# Main.net
KiCad netlist of a schematic drawn in Altium Designer
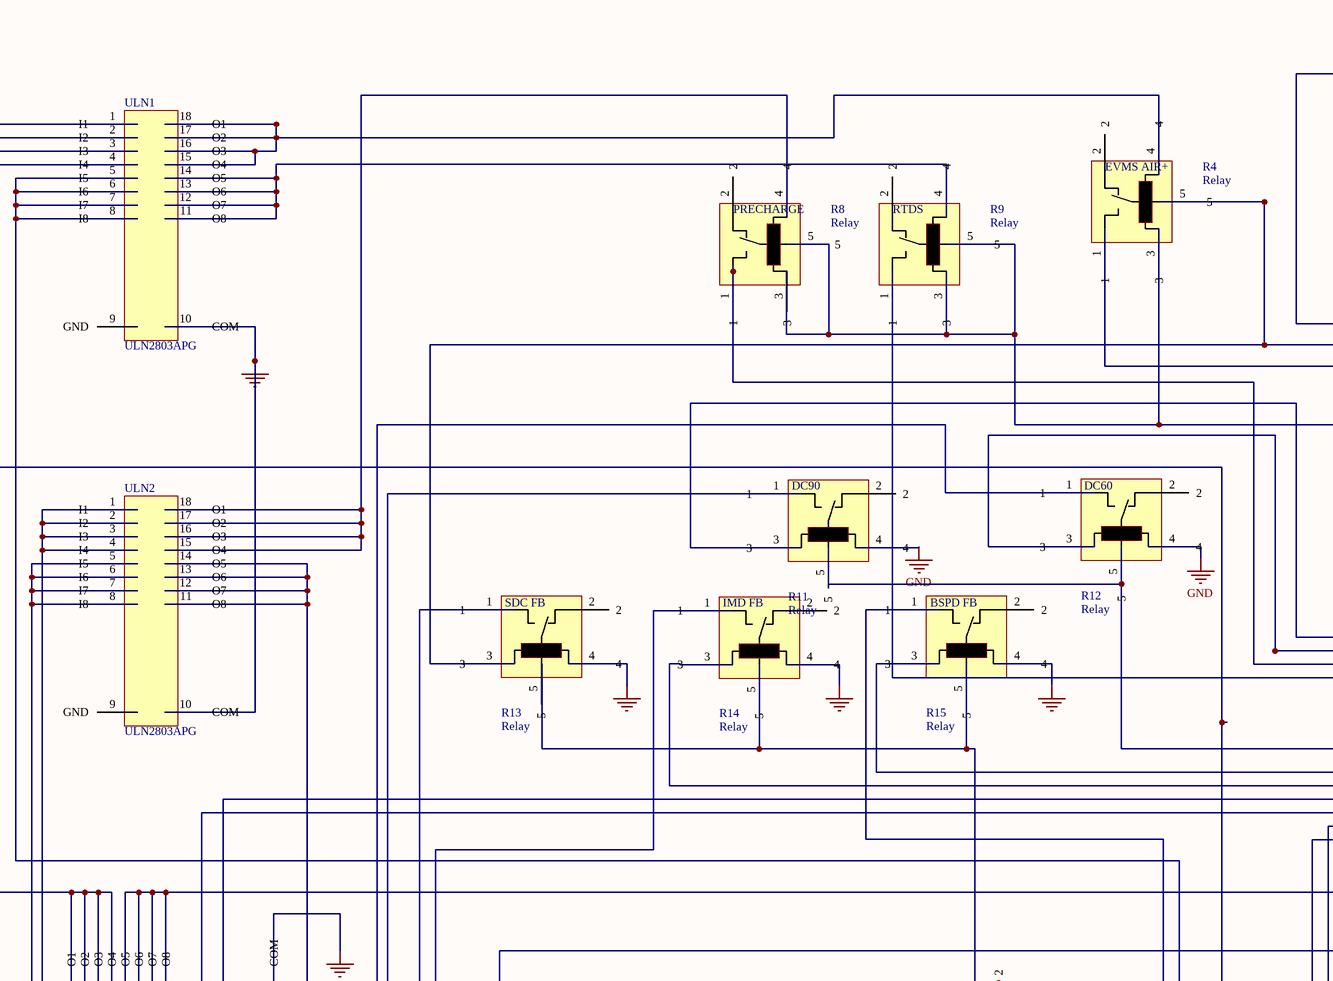
[diagram p0: Main.SchDoc, top left]
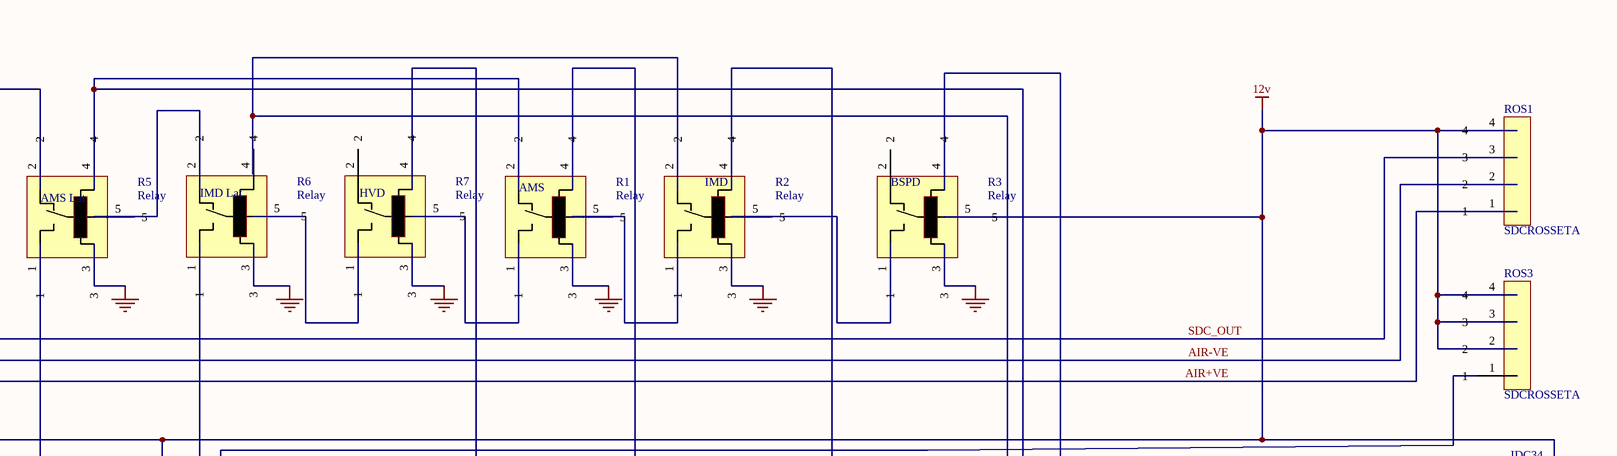
[diagram p1: Main.SchDoc, top right]
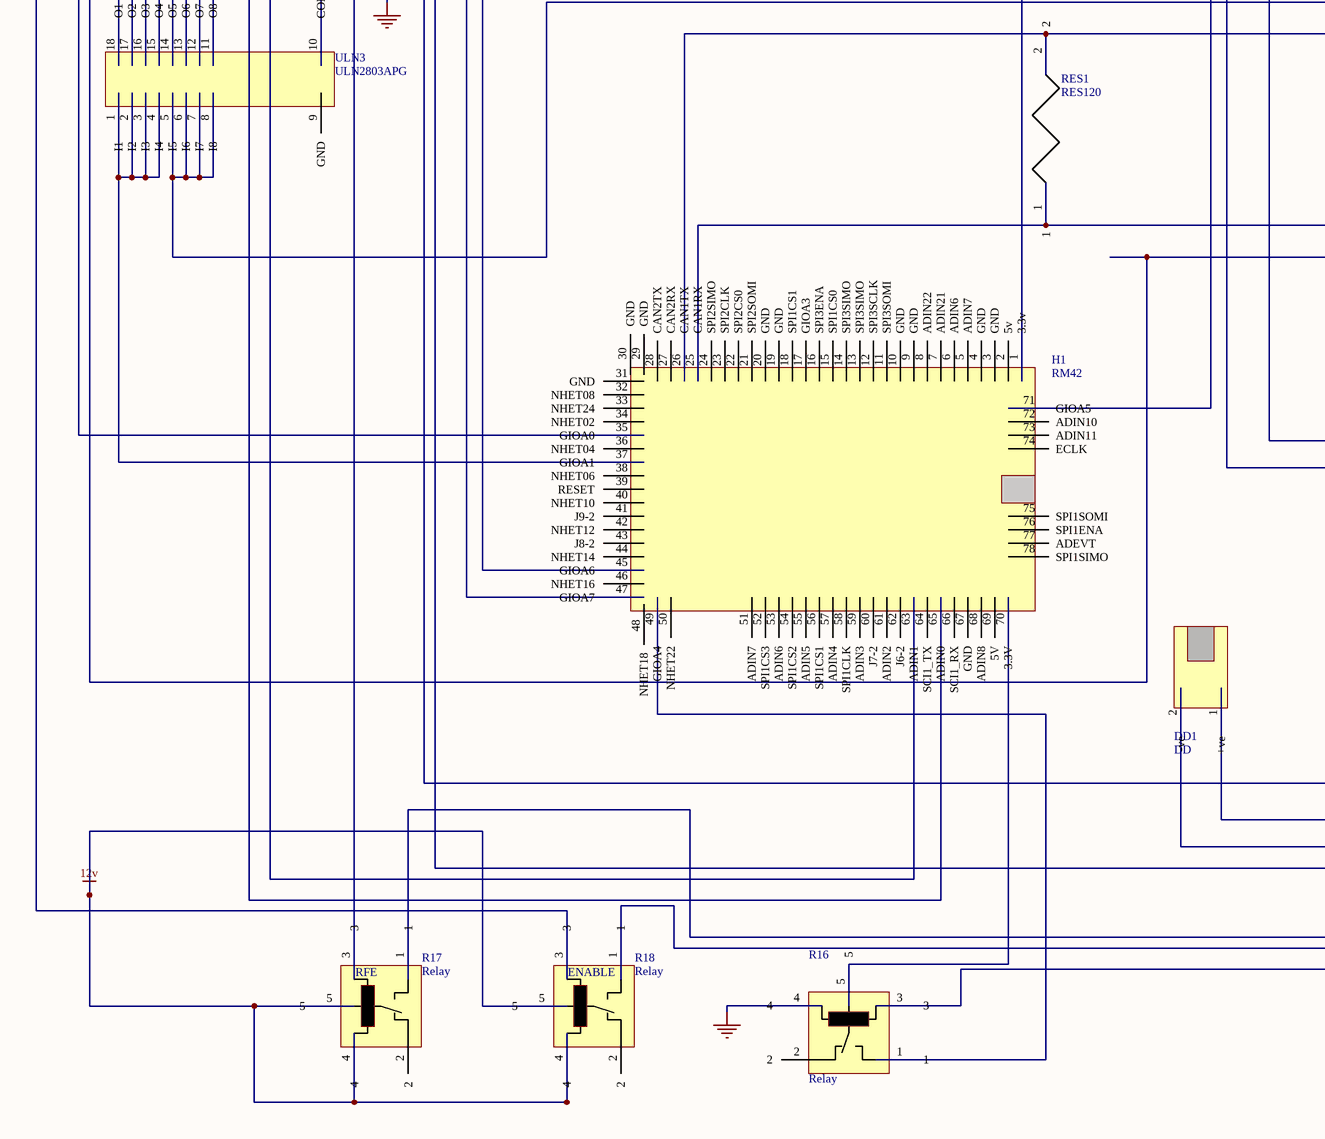
[diagram p2: Main.SchDoc, bottom left]
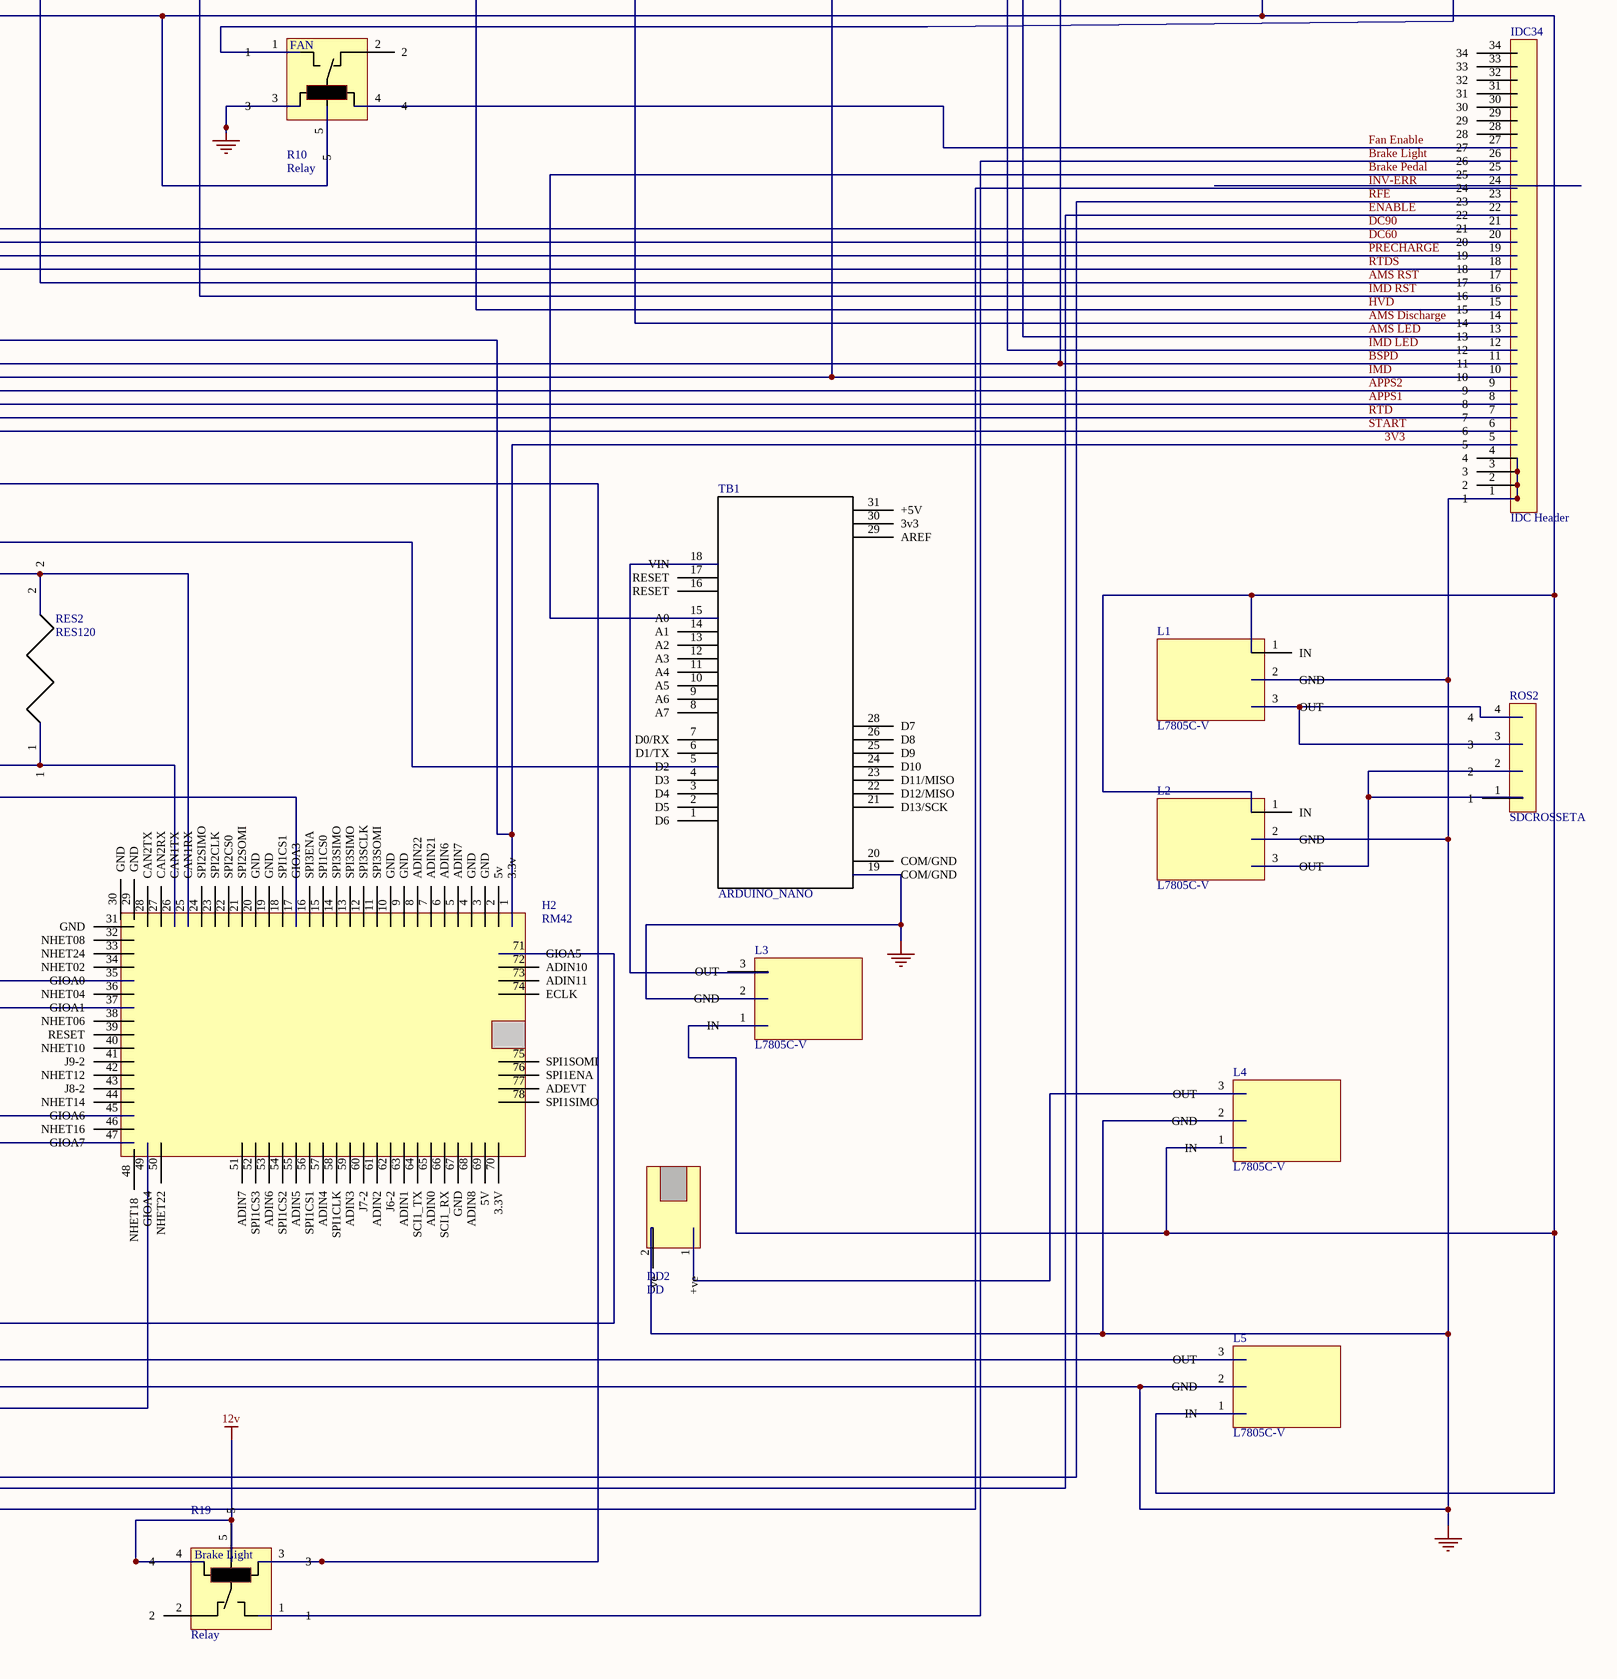
[diagram p3: Main.SchDoc, bottom right]

(export (version "E")
  (design (tool "Eeschema 10.0.6"))
  (components
    (comp (ref "DD1") (value "DD") (footprint "DCDCBoost") (libsource (lib "MainSchLib") (part "DCDCBoost")))
    (comp (ref "DD2") (value "DD") (footprint "DCDCBoost") (libsource (lib "MainSchLib") (part "DCDCBoost")))
    (comp (ref "H1") (value "RM42") (footprint "Hercules") (libsource (lib "MainSchLib") (part "Hercules")))
    (comp (ref "H2") (value "RM42") (footprint "Hercules") (libsource (lib "MainSchLib") (part "Hercules")))
    (comp (ref "IDC34")
      (value "IDC Header")
      (footprint "IDC34")
      (libsource (lib "MainSchLib") (part "IDC34"))
    )
    (comp (ref "L1")
      (value "L7805C-V")
      (footprint "L7805C-P")
      (description "STMICROELECTRONICS 	   	L7805CV 	   	Linear Voltage Regulators & Vref")
      (fields (field (name "MANUFACTURER") "STMicroelectronics") (field (name "TOLERANCE") "5%"))
      (libsource (lib "MainSchLib") (part "L7805C-V"))
    )
    (comp (ref "L2")
      (value "L7805C-V")
      (footprint "L7805C-P")
      (description "STMICROELECTRONICS 	   	L7805CV 	   	Linear Voltage Regulators & Vref")
      (fields (field (name "MANUFACTURER") "STMicroelectronics") (field (name "TOLERANCE") "5%"))
      (libsource (lib "MainSchLib") (part "L7805C-V"))
    )
    (comp (ref "L3")
      (value "L7805C-V")
      (footprint "L7805C-P")
      (description "STMICROELECTRONICS 	   	L7805CV 	   	Linear Voltage Regulators & Vref")
      (fields (field (name "MANUFACTURER") "STMicroelectronics") (field (name "TOLERANCE") "5%"))
      (libsource (lib "") (part "L7805C-V_1"))
    )
    (comp (ref "L4")
      (value "L7805C-V")
      (footprint "L7805C-P")
      (description "STMICROELECTRONICS 	   	L7805CV 	   	Linear Voltage Regulators & Vref")
      (fields (field (name "MANUFACTURER") "STMicroelectronics") (field (name "TOLERANCE") "5%"))
      (libsource (lib "") (part "L7805C-V_1"))
    )
    (comp (ref "L5")
      (value "L7805C-V")
      (footprint "L7805C-P")
      (description "STMICROELECTRONICS 	   	L7805CV 	   	Linear Voltage Regulators & Vref")
      (fields (field (name "MANUFACTURER") "STMicroelectronics") (field (name "TOLERANCE") "5%"))
      (libsource (lib "") (part "L7805C-V_1"))
    )
    (comp (ref "R1")
      (value "Relay")
      (footprint "RelayARP03F")
      (libsource (lib "MainSchLib") (part "RelayARP03F"))
    )
    (comp (ref "R2")
      (value "Relay")
      (footprint "RelayARP03F")
      (libsource (lib "MainSchLib") (part "RelayARP03F"))
    )
    (comp (ref "R3")
      (value "Relay")
      (footprint "RelayARP03F")
      (libsource (lib "MainSchLib") (part "RelayARP03F"))
    )
    (comp (ref "R4")
      (value "Relay")
      (footprint "RelayARP03F")
      (libsource (lib "MainSchLib") (part "RelayARP03F"))
    )
    (comp (ref "R5")
      (value "Relay")
      (footprint "RelayARP03F")
      (libsource (lib "MainSchLib") (part "RelayARP03F"))
    )
    (comp (ref "R6")
      (value "Relay")
      (footprint "RelayARP03F")
      (libsource (lib "MainSchLib") (part "RelayARP03F"))
    )
    (comp (ref "R7")
      (value "Relay")
      (footprint "RelayARP03F")
      (libsource (lib "MainSchLib") (part "RelayARP03F"))
    )
    (comp (ref "R8")
      (value "Relay")
      (footprint "RelayARP03F")
      (libsource (lib "MainSchLib") (part "RelayARP03F"))
    )
    (comp (ref "R9")
      (value "Relay")
      (footprint "RelayARP03F")
      (libsource (lib "MainSchLib") (part "RelayARP03F"))
    )
    (comp (ref "R10") (value "Relay") (footprint "RelayARP03F") (libsource (lib "") (part "RelayARP03F_1")))
    (comp (ref "R11") (value "Relay") (footprint "RelayARP03F") (libsource (lib "") (part "RelayARP03F_1")))
    (comp (ref "R12") (value "Relay") (footprint "RelayARP03F") (libsource (lib "") (part "RelayARP03F_1")))
    (comp (ref "R13") (value "Relay") (footprint "RelayARP03F") (libsource (lib "") (part "RelayARP03F_1")))
    (comp (ref "R14") (value "Relay") (footprint "RelayARP03F") (libsource (lib "") (part "RelayARP03F_1")))
    (comp (ref "R15") (value "Relay") (footprint "RelayARP03F") (libsource (lib "") (part "RelayARP03F_1")))
    (comp (ref "R16") (value "Relay") (footprint "RelayARP03F") (libsource (lib "") (part "RelayARP03F_3")))
    (comp (ref "R17") (value "Relay") (footprint "RelayARP03F") (libsource (lib "") (part "RelayARP03F_2")))
    (comp (ref "R18") (value "Relay") (footprint "RelayARP03F") (libsource (lib "") (part "RelayARP03F_2")))
    (comp (ref "R19") (value "Relay") (footprint "RelayARP03F") (libsource (lib "") (part "RelayARP03F_3")))
    (comp (ref "RES1")
      (value "RES120")
      (footprint "RES120")
      (description "Carbon Resistor 120.0 ohm 1/4W")
      (libsource (lib "MainSchLib") (part "RES120"))
    )
    (comp (ref "RES2")
      (value "RES120")
      (footprint "RES120")
      (description "Carbon Resistor 120.0 ohm 1/4W")
      (libsource (lib "MainSchLib") (part "RES120"))
    )
    (comp (ref "ROS1")
      (value "SDCROSSETA")
      (footprint "ROSSETA")
      (libsource (lib "MainSchLib") (part "SDCROSSETA"))
    )
    (comp (ref "ROS2")
      (value "SDCROSSETA")
      (footprint "ROSSETA")
      (libsource (lib "MainSchLib") (part "SDCROSSETA"))
    )
    (comp (ref "ROS3")
      (value "SDCROSSETA")
      (footprint "ROSSETA")
      (libsource (lib "MainSchLib") (part "SDCROSSETA"))
    )
    (comp (ref "TB1")
      (value "ARDUINO_NANO")
      (footprint "SHIELD_ARDUINO_NANO")
      (description "Dev.kit: Arduino; UART; ICSP, USB B mini, pin strips")
      (fields (field (name "MP") "ARDUINO NANO") (field (name "MF") "Arduino"))
      (libsource (lib "MainSchLib") (part "ARDUINO_NANO"))
    )
    (comp (ref "ULN1")
      (value "ULN2803APG")
      (footprint "ULN2803APG")
      (libsource (lib "MainSchLib") (part "ULN2803APG"))
    )
    (comp (ref "ULN2")
      (value "ULN2803APG")
      (footprint "ULN2803APG")
      (libsource (lib "MainSchLib") (part "ULN2803APG"))
    )
    (comp (ref "ULN3")
      (value "ULN2803APG")
      (footprint "ULN2803APG")
      (libsource (lib "") (part "ULN2803APG_1"))
    )
  )
  (nets
    (net (code "1") (name "/3V3") (class "Default")
      (node (ref "H2") (pin "1") (pinfunction "3.3v_1") (pintype "passive"))
      (node (ref "IDC34") (pin "5") (pinfunction "5_5") (pintype "passive"))
      (node (ref "R11") (pin "5") (pinfunction "5_5") (pintype "passive"))
      (node (ref "R12") (pin "5") (pinfunction "5_5") (pintype "passive"))
    )
    (net (code "2") (name "/AIR+VE") (class "Default")
      (node (ref "R4") (pin "1") (pinfunction "1_1") (pintype "passive"))
      (node (ref "ROS1") (pin "1") (pinfunction "1_1") (pintype "passive"))
    )
    (net (code "3") (name "/AIR-VE") (class "Default")
      (node (ref "R13") (pin "3") (pinfunction "3_3") (pintype "passive"))
      (node (ref "R4") (pin "5") (pinfunction "5_5") (pintype "passive"))
      (node (ref "ROS1") (pin "2") (pinfunction "2_2") (pintype "passive"))
    )
    (net (code "4") (name "/AMS Discharge") (class "Default")
      (node (ref "IDC34") (pin "14") (pinfunction "14_14") (pintype "passive"))
      (node (ref "R1") (pin "4") (pinfunction "4_4") (pintype "passive"))
    )
    (net (code "5") (name "/AMS LED") (class "Default")
      (node (ref "IDC34") (pin "13") (pinfunction "13_13") (pintype "passive"))
      (node (ref "R1") (pin "2") (pinfunction "2_2") (pintype "passive"))
      (node (ref "R5") (pin "4") (pinfunction "4_4") (pintype "passive"))
    )
    (net (code "6") (name "/AMS RST") (class "Default")
      (node (ref "IDC34") (pin "17") (pinfunction "17_17") (pintype "passive"))
      (node (ref "R5") (pin "1") (pinfunction "1_1") (pintype "passive"))
    )
    (net (code "7") (name "/APPS1") (class "Default")
      (node (ref "H1") (pin "65") (pinfunction "ADIN0_65") (pintype "passive"))
      (node (ref "IDC34") (pin "8") (pinfunction "8_8") (pintype "passive"))
    )
    (net (code "8") (name "/APPS2") (class "Default")
      (node (ref "H1") (pin "63") (pinfunction "ADIN1_63") (pintype "passive"))
      (node (ref "IDC34") (pin "9") (pinfunction "9_9") (pintype "passive"))
    )
    (net (code "9") (name "/BSPD") (class "Default")
      (node (ref "IDC34") (pin "11") (pinfunction "11_11") (pintype "passive"))
      (node (ref "R15") (pin "3") (pinfunction "3_3") (pintype "passive"))
      (node (ref "R3") (pin "4") (pinfunction "4_4") (pintype "passive"))
    )
    (net (code "10") (name "/Brake Light") (class "Default")
      (node (ref "IDC34") (pin "26") (pinfunction "26_26") (pintype "passive"))
      (node (ref "R19") (pin "1") (pinfunction "1_1") (pintype "passive"))
    )
    (net (code "11") (name "/Brake Pedal") (class "Default")
      (node (ref "IDC34") (pin "25") (pinfunction "25_25") (pintype "passive"))
      (node (ref "TB1") (pin "15") (pinfunction "A0_15") (pintype "passive"))
    )
    (net (code "12") (name "/DC60") (class "Default")
      (node (ref "IDC34") (pin "20") (pinfunction "20_20") (pintype "passive"))
      (node (ref "R12") (pin "3") (pinfunction "3_3") (pintype "passive"))
    )
    (net (code "13") (name "/DC90") (class "Default")
      (node (ref "IDC34") (pin "21") (pinfunction "21_21") (pintype "passive"))
      (node (ref "R11") (pin "3") (pinfunction "3_3") (pintype "passive"))
    )
    (net (code "14") (name "/ENABLE") (class "Default")
      (node (ref "IDC34") (pin "22") (pinfunction "22_22") (pintype "passive"))
      (node (ref "R18") (pin "1") (pinfunction "1_1") (pintype "passive"))
    )
    (net (code "15") (name "/Fan Enable") (class "Default")
      (node (ref "IDC34") (pin "27") (pinfunction "27_27") (pintype "passive"))
      (node (ref "R10") (pin "4") (pinfunction "4_4") (pintype "passive"))
    )
    (net (code "16") (name "/HVD") (class "Default")
      (node (ref "IDC34") (pin "15") (pinfunction "15_15") (pintype "passive"))
      (node (ref "R7") (pin "4") (pinfunction "4_4") (pintype "passive"))
    )
    (net (code "17") (name "/IMD") (class "Default")
      (node (ref "IDC34") (pin "10") (pinfunction "10_10") (pintype "passive"))
      (node (ref "R14") (pin "3") (pinfunction "3_3") (pintype "passive"))
      (node (ref "R2") (pin "4") (pinfunction "4_4") (pintype "passive"))
    )
    (net (code "18") (name "/IMD LED") (class "Default")
      (node (ref "IDC34") (pin "12") (pinfunction "12_12") (pintype "passive"))
      (node (ref "R2") (pin "2") (pinfunction "2_2") (pintype "passive"))
    )
    (net (code "19") (name "/IMD RST") (class "Default")
      (node (ref "IDC34") (pin "16") (pinfunction "16_16") (pintype "passive"))
      (node (ref "R6") (pin "1") (pinfunction "1_1") (pintype "passive"))
    )
    (net (code "20") (name "/INV-ERR") (class "Default")
      (node (ref "IDC34") (pin "24") (pinfunction "24_24") (pintype "passive"))
      (node (ref "R16") (pin "3") (pinfunction "3_3") (pintype "passive"))
    )
    (net (code "21") (name "/PRECHARGE") (class "Default")
      (node (ref "IDC34") (pin "19") (pinfunction "19_19") (pintype "passive"))
      (node (ref "R8") (pin "1") (pinfunction "1_1") (pintype "passive"))
    )
    (net (code "22") (name "/RFE") (class "Default")
      (node (ref "IDC34") (pin "23") (pinfunction "23_23") (pintype "passive"))
      (node (ref "R17") (pin "1") (pinfunction "1_1") (pintype "passive"))
    )
    (net (code "23") (name "/RTD") (class "Default")
      (node (ref "H2") (pin "47") (pinfunction "GIOA7_47") (pintype "passive"))
      (node (ref "IDC34") (pin "7") (pinfunction "7_7") (pintype "passive"))
    )
    (net (code "24") (name "/RTDS") (class "Default")
      (node (ref "IDC34") (pin "18") (pinfunction "18_18") (pintype "passive"))
      (node (ref "R9") (pin "1") (pinfunction "1_1") (pintype "passive"))
    )
    (net (code "25") (name "/SDC_OUT") (class "Default")
      (node (ref "R5") (pin "2") (pinfunction "2_2") (pintype "passive"))
      (node (ref "ROS1") (pin "3") (pinfunction "3_3") (pintype "passive"))
    )
    (net (code "26") (name "/START") (class "Default")
      (node (ref "H2") (pin "45") (pinfunction "GIOA6_45") (pintype "passive"))
      (node (ref "IDC34") (pin "6") (pinfunction "6_6") (pintype "passive"))
    )
    (net (code "27") (name "12v") (class "Default")
      (node (ref "L1") (pin "1") (pinfunction "IN_1") (pintype "passive"))
      (node (ref "L2") (pin "1") (pinfunction "IN_1") (pintype "passive"))
      (node (ref "L3") (pin "1") (pinfunction "IN_1") (pintype "passive"))
      (node (ref "L4") (pin "1") (pinfunction "IN_1") (pintype "passive"))
      (node (ref "L5") (pin "1") (pinfunction "IN_1") (pintype "passive"))
      (node (ref "R10") (pin "5") (pinfunction "5_5") (pintype "passive"))
      (node (ref "R17") (pin "4") (pinfunction "4_4") (pintype "passive"))
      (node (ref "R17") (pin "5") (pinfunction "5_5") (pintype "passive"))
      (node (ref "R18") (pin "4") (pinfunction "4_4") (pintype "passive"))
      (node (ref "R18") (pin "5") (pinfunction "5_5") (pintype "passive"))
      (node (ref "R19") (pin "4") (pinfunction "4_4") (pintype "passive"))
      (node (ref "R19") (pin "5") (pinfunction "5_5") (pintype "passive"))
      (node (ref "R3") (pin "5") (pinfunction "5_5") (pintype "passive"))
      (node (ref "R4") (pin "3") (pinfunction "3_3") (pintype "passive"))
      (node (ref "R8") (pin "3") (pinfunction "3_3") (pintype "passive"))
      (node (ref "R8") (pin "5") (pinfunction "5_5") (pintype "passive"))
      (node (ref "R9") (pin "3") (pinfunction "3_3") (pintype "passive"))
      (node (ref "R9") (pin "5") (pinfunction "5_5") (pintype "passive"))
      (node (ref "ROS1") (pin "4") (pinfunction "4_4") (pintype "passive"))
      (node (ref "ROS3") (pin "2") (pinfunction "2_2") (pintype "passive"))
      (node (ref "ROS3") (pin "3") (pinfunction "3_3") (pintype "passive"))
      (node (ref "ROS3") (pin "4") (pinfunction "4_4") (pintype "passive"))
    )
    (net (code "28") (name "GND") (class "Default")
      (node (ref "DD1") (pin "2") (pinfunction "-ve_2") (pintype "passive"))
      (node (ref "DD2") (pin "2") (pinfunction "-ve_2") (pintype "passive"))
      (node (ref "IDC34") (pin "1") (pinfunction "1_1") (pintype "passive"))
      (node (ref "IDC34") (pin "2") (pinfunction "2_2") (pintype "passive"))
      (node (ref "IDC34") (pin "3") (pinfunction "3_3") (pintype "passive"))
      (node (ref "IDC34") (pin "4") (pinfunction "4_4") (pintype "passive"))
      (node (ref "L1") (pin "2") (pinfunction "GND_2") (pintype "passive"))
      (node (ref "L2") (pin "2") (pinfunction "GND_2") (pintype "passive"))
      (node (ref "L3") (pin "2") (pinfunction "GND_2") (pintype "passive"))
      (node (ref "L4") (pin "2") (pinfunction "GND_2") (pintype "passive"))
      (node (ref "L5") (pin "2") (pinfunction "GND_2") (pintype "passive"))
      (node (ref "R1") (pin "3") (pinfunction "3_3") (pintype "passive"))
      (node (ref "R10") (pin "3") (pinfunction "3_3") (pintype "passive"))
      (node (ref "R11") (pin "4") (pinfunction "4_4") (pintype "passive"))
      (node (ref "R12") (pin "4") (pinfunction "4_4") (pintype "passive"))
      (node (ref "R13") (pin "4") (pinfunction "4_4") (pintype "passive"))
      (node (ref "R14") (pin "4") (pinfunction "4_4") (pintype "passive"))
      (node (ref "R15") (pin "4") (pinfunction "4_4") (pintype "passive"))
      (node (ref "R16") (pin "4") (pinfunction "4_4") (pintype "passive"))
      (node (ref "R2") (pin "3") (pinfunction "3_3") (pintype "passive"))
      (node (ref "R3") (pin "3") (pinfunction "3_3") (pintype "passive"))
      (node (ref "R5") (pin "3") (pinfunction "3_3") (pintype "passive"))
      (node (ref "R6") (pin "3") (pinfunction "3_3") (pintype "passive"))
      (node (ref "R7") (pin "3") (pinfunction "3_3") (pintype "passive"))
      (node (ref "TB1") (pin "19") (pinfunction "COM/GND_19") (pintype "passive"))
      (node (ref "ULN1") (pin "10") (pinfunction "COM_10") (pintype "passive"))
      (node (ref "ULN2") (pin "10") (pinfunction "COM_10") (pintype "passive"))
      (node (ref "ULN3") (pin "10") (pinfunction "COM_10") (pintype "passive"))
    )
    (net (code "29") (name "Net-(DD1-+ve)") (class "Default")
      (node (ref "DD1") (pin "1") (pinfunction "+ve_1") (pintype "passive"))
      (node (ref "L5") (pin "3") (pinfunction "OUT_3") (pintype "passive"))
    )
    (net (code "30") (name "Net-(DD2-+ve)") (class "Default")
      (node (ref "DD2") (pin "1") (pinfunction "+ve_1") (pintype "passive"))
      (node (ref "L4") (pin "3") (pinfunction "OUT_3") (pintype "passive"))
    )
    (net (code "31") (name "Net-(H1-3.3V)") (class "Default")
      (node (ref "H1") (pin "70") (pinfunction "3.3V_70") (pintype "passive"))
      (node (ref "R16") (pin "5") (pinfunction "5_5") (pintype "passive"))
    )
    (net (code "32") (name "Net-(H1-3.3v)") (class "Default")
      (node (ref "H1") (pin "1") (pinfunction "3.3v_1") (pintype "passive"))
      (node (ref "R13") (pin "5") (pinfunction "5_5") (pintype "passive"))
      (node (ref "R14") (pin "5") (pinfunction "5_5") (pintype "passive"))
      (node (ref "R15") (pin "5") (pinfunction "5_5") (pintype "passive"))
    )
    (net (code "33") (name "Net-(H1-CAN1RX)") (class "Default")
      (node (ref "H1") (pin "25") (pinfunction "CAN1RX_25") (pintype "passive"))
      (node (ref "H2") (pin "26") (pinfunction "CAN1TX_26") (pintype "passive"))
      (node (ref "RES1") (pin "1") (pinfunction "1_1") (pintype "passive"))
      (node (ref "RES2") (pin "1") (pinfunction "1_1") (pintype "passive"))
    )
    (net (code "34") (name "Net-(H1-CAN1TX)") (class "Default")
      (node (ref "H1") (pin "26") (pinfunction "CAN1TX_26") (pintype "passive"))
      (node (ref "H2") (pin "25") (pinfunction "CAN1RX_25") (pintype "passive"))
      (node (ref "RES1") (pin "2") (pinfunction "2_2") (pintype "passive"))
      (node (ref "RES2") (pin "2") (pinfunction "2_2") (pintype "passive"))
    )
    (net (code "35") (name "Net-(H1-GIOA0)") (class "Default")
      (node (ref "H1") (pin "35") (pinfunction "GIOA0_35") (pintype "passive"))
      (node (ref "ULN2") (pin "5") (pinfunction "I5_5") (pintype "passive"))
      (node (ref "ULN2") (pin "6") (pinfunction "I6_6") (pintype "passive"))
      (node (ref "ULN2") (pin "7") (pinfunction "I7_7") (pintype "passive"))
      (node (ref "ULN2") (pin "8") (pinfunction "I8_8") (pintype "passive"))
    )
    (net (code "36") (name "Net-(H1-GIOA1)") (class "Default")
      (node (ref "H1") (pin "37") (pinfunction "GIOA1_37") (pintype "passive"))
      (node (ref "ULN3") (pin "1") (pinfunction "I1_1") (pintype "passive"))
      (node (ref "ULN3") (pin "2") (pinfunction "I2_2") (pintype "passive"))
      (node (ref "ULN3") (pin "3") (pinfunction "I3_3") (pintype "passive"))
      (node (ref "ULN3") (pin "4") (pinfunction "I4_4") (pintype "passive"))
    )
    (net (code "37") (name "Net-(H1-GIOA4)") (class "Default")
      (node (ref "H1") (pin "49") (pinfunction "GIOA4_49") (pintype "passive"))
      (node (ref "R16") (pin "1") (pinfunction "1_1") (pintype "passive"))
    )
    (net (code "38") (name "Net-(H1-GIOA5)") (class "Default")
      (node (ref "H1") (pin "71") (pinfunction "GIOA5_71") (pintype "passive"))
      (node (ref "R15") (pin "1") (pinfunction "1_1") (pintype "passive"))
    )
    (net (code "39") (name "Net-(H1-GIOA6)") (class "Default")
      (node (ref "H1") (pin "45") (pinfunction "GIOA6_45") (pintype "passive"))
      (node (ref "R14") (pin "1") (pinfunction "1_1") (pintype "passive"))
    )
    (net (code "40") (name "Net-(H1-GIOA7)") (class "Default")
      (node (ref "H1") (pin "47") (pinfunction "GIOA7_47") (pintype "passive"))
      (node (ref "R13") (pin "1") (pinfunction "1_1") (pintype "passive"))
    )
    (net (code "41") (name "Net-(H2-GIOA0)") (class "Default")
      (node (ref "H2") (pin "35") (pinfunction "GIOA0_35") (pintype "passive"))
      (node (ref "ULN1") (pin "1") (pinfunction "I1_1") (pintype "passive"))
      (node (ref "ULN1") (pin "2") (pinfunction "I2_2") (pintype "passive"))
      (node (ref "ULN1") (pin "3") (pinfunction "I3_3") (pintype "passive"))
      (node (ref "ULN1") (pin "4") (pinfunction "I4_4") (pintype "passive"))
    )
    (net (code "42") (name "Net-(H2-GIOA1)") (class "Default")
      (node (ref "H2") (pin "37") (pinfunction "GIOA1_37") (pintype "passive"))
      (node (ref "ULN1") (pin "5") (pinfunction "I5_5") (pintype "passive"))
      (node (ref "ULN1") (pin "6") (pinfunction "I6_6") (pintype "passive"))
      (node (ref "ULN1") (pin "7") (pinfunction "I7_7") (pintype "passive"))
      (node (ref "ULN1") (pin "8") (pinfunction "I8_8") (pintype "passive"))
    )
    (net (code "43") (name "Net-(H2-GIOA3)") (class "Default")
      (node (ref "H2") (pin "17") (pinfunction "GIOA3_17") (pintype "passive"))
      (node (ref "ULN2") (pin "1") (pinfunction "I1_1") (pintype "passive"))
      (node (ref "ULN2") (pin "2") (pinfunction "I2_2") (pintype "passive"))
      (node (ref "ULN2") (pin "3") (pinfunction "I3_3") (pintype "passive"))
      (node (ref "ULN2") (pin "4") (pinfunction "I4_4") (pintype "passive"))
    )
    (net (code "44") (name "Net-(H2-GIOA4)") (class "Default")
      (node (ref "H2") (pin "49") (pinfunction "GIOA4_49") (pintype "passive"))
      (node (ref "R11") (pin "1") (pinfunction "1_1") (pintype "passive"))
    )
    (net (code "45") (name "Net-(H2-GIOA5)") (class "Default")
      (node (ref "H2") (pin "71") (pinfunction "GIOA5_71") (pintype "passive"))
      (node (ref "R12") (pin "1") (pinfunction "1_1") (pintype "passive"))
    )
    (net (code "46") (name "Net-(L1-OUT)") (class "Default")
      (node (ref "L1") (pin "3") (pinfunction "OUT_3") (pintype "passive"))
      (node (ref "ROS2") (pin "3") (pinfunction "3_3") (pintype "passive"))
      (node (ref "ROS2") (pin "4") (pinfunction "4_4") (pintype "passive"))
    )
    (net (code "47") (name "Net-(L2-OUT)") (class "Default")
      (node (ref "L2") (pin "3") (pinfunction "OUT_3") (pintype "passive"))
      (node (ref "ROS2") (pin "1") (pinfunction "1_1") (pintype "passive"))
      (node (ref "ROS2") (pin "2") (pinfunction "2_2") (pintype "passive"))
    )
    (net (code "48") (name "Net-(L3-OUT)") (class "Default")
      (node (ref "L3") (pin "3") (pinfunction "OUT_3") (pintype "passive"))
      (node (ref "TB1") (pin "18") (pinfunction "VIN_18") (pintype "passive"))
    )
    (net (code "49") (name "Net-(R1-Pad1)") (class "Default")
      (node (ref "R1") (pin "1") (pinfunction "1_1") (pintype "passive"))
      (node (ref "R7") (pin "5") (pinfunction "5_5") (pintype "passive"))
    )
    (net (code "50") (name "Net-(R1-Pad5)") (class "Default")
      (node (ref "R1") (pin "5") (pinfunction "5_5") (pintype "passive"))
      (node (ref "R2") (pin "1") (pinfunction "1_1") (pintype "passive"))
    )
    (net (code "51") (name "Net-(R2-Pad5)") (class "Default")
      (node (ref "R2") (pin "5") (pinfunction "5_5") (pintype "passive"))
      (node (ref "R3") (pin "1") (pinfunction "1_1") (pintype "passive"))
    )
    (net (code "52") (name "Net-(R5-Pad5)") (class "Default")
      (node (ref "R5") (pin "5") (pinfunction "5_5") (pintype "passive"))
      (node (ref "R6") (pin "2") (pinfunction "2_2") (pintype "passive"))
    )
    (net (code "53") (name "Net-(R6-Pad5)") (class "Default")
      (node (ref "R6") (pin "5") (pinfunction "5_5") (pintype "passive"))
      (node (ref "R7") (pin "1") (pinfunction "1_1") (pintype "passive"))
    )
    (net (code "54") (name "Net-(R10-Pad1)") (class "Default")
      (node (ref "R10") (pin "1") (pinfunction "1_1") (pintype "passive"))
      (node (ref "ROS3") (pin "1") (pinfunction "1_1") (pintype "passive"))
    )
    (net (code "55") (name "Net-(TB1-D2)") (class "Default")
      (node (ref "TB1") (pin "5") (pinfunction "D2_5") (pintype "passive"))
      (node (ref "ULN3") (pin "5") (pinfunction "I5_5") (pintype "passive"))
      (node (ref "ULN3") (pin "6") (pinfunction "I6_6") (pintype "passive"))
      (node (ref "ULN3") (pin "7") (pinfunction "I7_7") (pintype "passive"))
      (node (ref "ULN3") (pin "8") (pinfunction "I8_8") (pintype "passive"))
    )
    (net (code "56") (name "Net-(ULN1-O1)") (class "Default")
      (node (ref "R4") (pin "4") (pinfunction "4_4") (pintype "passive"))
      (node (ref "ULN1") (pin "15") (pinfunction "O4_15") (pintype "passive"))
      (node (ref "ULN1") (pin "16") (pinfunction "O3_16") (pintype "passive"))
      (node (ref "ULN1") (pin "17") (pinfunction "O2_17") (pintype "passive"))
      (node (ref "ULN1") (pin "18") (pinfunction "O1_18") (pintype "passive"))
    )
    (net (code "57") (name "Net-(ULN1-O5)") (class "Default")
      (node (ref "R9") (pin "4") (pinfunction "4_4") (pintype "passive"))
      (node (ref "ULN1") (pin "11") (pinfunction "O8_11") (pintype "passive"))
      (node (ref "ULN1") (pin "12") (pinfunction "O7_12") (pintype "passive"))
      (node (ref "ULN1") (pin "13") (pinfunction "O6_13") (pintype "passive"))
      (node (ref "ULN1") (pin "14") (pinfunction "O5_14") (pintype "passive"))
    )
    (net (code "58") (name "Net-(ULN2-O1)") (class "Default")
      (node (ref "R8") (pin "4") (pinfunction "4_4") (pintype "passive"))
      (node (ref "ULN2") (pin "15") (pinfunction "O4_15") (pintype "passive"))
      (node (ref "ULN2") (pin "16") (pinfunction "O3_16") (pintype "passive"))
      (node (ref "ULN2") (pin "17") (pinfunction "O2_17") (pintype "passive"))
      (node (ref "ULN2") (pin "18") (pinfunction "O1_18") (pintype "passive"))
    )
    (net (code "59") (name "Net-(ULN2-O5)") (class "Default")
      (node (ref "R17") (pin "3") (pinfunction "3_3") (pintype "passive"))
      (node (ref "ULN2") (pin "11") (pinfunction "O8_11") (pintype "passive"))
      (node (ref "ULN2") (pin "12") (pinfunction "O7_12") (pintype "passive"))
      (node (ref "ULN2") (pin "13") (pinfunction "O6_13") (pintype "passive"))
      (node (ref "ULN2") (pin "14") (pinfunction "O5_14") (pintype "passive"))
    )
    (net (code "60") (name "Net-(ULN3-O1)") (class "Default")
      (node (ref "R18") (pin "3") (pinfunction "3_3") (pintype "passive"))
      (node (ref "ULN3") (pin "15") (pinfunction "O4_15") (pintype "passive"))
      (node (ref "ULN3") (pin "16") (pinfunction "O3_16") (pintype "passive"))
      (node (ref "ULN3") (pin "17") (pinfunction "O2_17") (pintype "passive"))
      (node (ref "ULN3") (pin "18") (pinfunction "O1_18") (pintype "passive"))
    )
    (net (code "61") (name "Net-(ULN3-O5)") (class "Default")
      (node (ref "R19") (pin "3") (pinfunction "3_3") (pintype "passive"))
      (node (ref "ULN3") (pin "11") (pinfunction "O8_11") (pintype "passive"))
      (node (ref "ULN3") (pin "12") (pinfunction "O7_12") (pintype "passive"))
      (node (ref "ULN3") (pin "13") (pinfunction "O6_13") (pintype "passive"))
      (node (ref "ULN3") (pin "14") (pinfunction "O5_14") (pintype "passive"))
    )
    (net (code "62") (name "unconnected-(H1-5V-Pad69)") (class "Default")
      (node (ref "H1") (pin "69") (pinfunction "5V_69") (pintype "passive"))
    )
    (net (code "63") (name "unconnected-(H1-5v-Pad2)") (class "Default")
      (node (ref "H1") (pin "2") (pinfunction "5v_2") (pintype "passive"))
    )
    (net (code "64") (name "unconnected-(H1-ADEVT-Pad77)") (class "Default")
      (node (ref "H1") (pin "77") (pinfunction "ADEVT_77") (pintype "passive"))
    )
    (net (code "65") (name "unconnected-(H1-ADIN2-Pad61)") (class "Default")
      (node (ref "H1") (pin "61") (pinfunction "ADIN2_61") (pintype "passive"))
    )
    (net (code "66") (name "unconnected-(H1-ADIN3-Pad59)") (class "Default")
      (node (ref "H1") (pin "59") (pinfunction "ADIN3_59") (pintype "passive"))
    )
    (net (code "67") (name "unconnected-(H1-ADIN4-Pad57)") (class "Default")
      (node (ref "H1") (pin "57") (pinfunction "ADIN4_57") (pintype "passive"))
    )
    (net (code "68") (name "unconnected-(H1-ADIN5-Pad55)") (class "Default")
      (node (ref "H1") (pin "55") (pinfunction "ADIN5_55") (pintype "passive"))
    )
    (net (code "69") (name "unconnected-(H1-ADIN6-Pad6)") (class "Default")
      (node (ref "H1") (pin "6") (pinfunction "ADIN6_6") (pintype "passive"))
    )
    (net (code "70") (name "unconnected-(H1-ADIN6-Pad53)") (class "Default")
      (node (ref "H1") (pin "53") (pinfunction "ADIN6_53") (pintype "passive"))
    )
    (net (code "71") (name "unconnected-(H1-ADIN7-Pad5)") (class "Default")
      (node (ref "H1") (pin "5") (pinfunction "ADIN7_5") (pintype "passive"))
    )
    (net (code "72") (name "unconnected-(H1-ADIN7-Pad51)") (class "Default")
      (node (ref "H1") (pin "51") (pinfunction "ADIN7_51") (pintype "passive"))
    )
    (net (code "73") (name "unconnected-(H1-ADIN8-Pad68)") (class "Default")
      (node (ref "H1") (pin "68") (pinfunction "ADIN8_68") (pintype "passive"))
    )
    (net (code "74") (name "unconnected-(H1-ADIN10-Pad72)") (class "Default")
      (node (ref "H1") (pin "72") (pinfunction "ADIN10_72") (pintype "passive"))
    )
    (net (code "75") (name "unconnected-(H1-ADIN11-Pad73)") (class "Default")
      (node (ref "H1") (pin "73") (pinfunction "ADIN11_73") (pintype "passive"))
    )
    (net (code "76") (name "unconnected-(H1-ADIN21-Pad7)") (class "Default")
      (node (ref "H1") (pin "7") (pinfunction "ADIN21_7") (pintype "passive"))
    )
    (net (code "77") (name "unconnected-(H1-ADIN22-Pad8)") (class "Default")
      (node (ref "H1") (pin "8") (pinfunction "ADIN22_8") (pintype "passive"))
    )
    (net (code "78") (name "unconnected-(H1-CAN2RX-Pad27)") (class "Default")
      (node (ref "H1") (pin "27") (pinfunction "CAN2RX_27") (pintype "passive"))
    )
    (net (code "79") (name "unconnected-(H1-CAN2TX-Pad28)") (class "Default")
      (node (ref "H1") (pin "28") (pinfunction "CAN2TX_28") (pintype "passive"))
    )
    (net (code "80") (name "unconnected-(H1-ECLK-Pad74)") (class "Default")
      (node (ref "H1") (pin "74") (pinfunction "ECLK_74") (pintype "passive"))
    )
    (net (code "81") (name "unconnected-(H1-GIOA3-Pad17)") (class "Default")
      (node (ref "H1") (pin "17") (pinfunction "GIOA3_17") (pintype "passive"))
    )
    (net (code "82") (name "unconnected-(H1-GND-Pad3)") (class "Default")
      (node (ref "H1") (pin "3") (pinfunction "GND_3") (pintype "passive"))
    )
    (net (code "83") (name "unconnected-(H1-GND-Pad4)") (class "Default")
      (node (ref "H1") (pin "4") (pinfunction "GND_4") (pintype "passive"))
    )
    (net (code "84") (name "unconnected-(H1-GND-Pad9)") (class "Default")
      (node (ref "H1") (pin "9") (pinfunction "GND_9") (pintype "passive"))
    )
    (net (code "85") (name "unconnected-(H1-GND-Pad10)") (class "Default")
      (node (ref "H1") (pin "10") (pinfunction "GND_10") (pintype "passive"))
    )
    (net (code "86") (name "unconnected-(H1-GND-Pad19)") (class "Default")
      (node (ref "H1") (pin "19") (pinfunction "GND_19") (pintype "passive"))
    )
    (net (code "87") (name "unconnected-(H1-GND-Pad20)") (class "Default")
      (node (ref "H1") (pin "20") (pinfunction "GND_20") (pintype "passive"))
    )
    (net (code "88") (name "unconnected-(H1-GND-Pad29)") (class "Default")
      (node (ref "H1") (pin "29") (pinfunction "GND_29") (pintype "passive"))
    )
    (net (code "89") (name "unconnected-(H1-GND-Pad30)") (class "Default")
      (node (ref "H1") (pin "30") (pinfunction "GND_30") (pintype "passive"))
    )
    (net (code "90") (name "unconnected-(H1-GND-Pad31)") (class "Default")
      (node (ref "H1") (pin "31") (pinfunction "GND_31") (pintype "passive"))
    )
    (net (code "91") (name "unconnected-(H1-GND-Pad67)") (class "Default")
      (node (ref "H1") (pin "67") (pinfunction "GND_67") (pintype "passive"))
    )
    (net (code "92") (name "unconnected-(H1-J6-2-Pad62)") (class "Default")
      (node (ref "H1") (pin "62") (pinfunction "J6-2_62") (pintype "passive"))
    )
    (net (code "93") (name "unconnected-(H1-J7-2-Pad60)") (class "Default")
      (node (ref "H1") (pin "60") (pinfunction "J7-2_60") (pintype "passive"))
    )
    (net (code "94") (name "unconnected-(H1-J8-2-Pad43)") (class "Default")
      (node (ref "H1") (pin "43") (pinfunction "J8-2_43") (pintype "passive"))
    )
    (net (code "95") (name "unconnected-(H1-J9-2-Pad41)") (class "Default")
      (node (ref "H1") (pin "41") (pinfunction "J9-2_41") (pintype "passive"))
    )
    (net (code "96") (name "unconnected-(H1-NHET02-Pad34)") (class "Default")
      (node (ref "H1") (pin "34") (pinfunction "NHET02_34") (pintype "passive"))
    )
    (net (code "97") (name "unconnected-(H1-NHET04-Pad36)") (class "Default")
      (node (ref "H1") (pin "36") (pinfunction "NHET04_36") (pintype "passive"))
    )
    (net (code "98") (name "unconnected-(H1-NHET06-Pad38)") (class "Default")
      (node (ref "H1") (pin "38") (pinfunction "NHET06_38") (pintype "passive"))
    )
    (net (code "99") (name "unconnected-(H1-NHET08-Pad32)") (class "Default")
      (node (ref "H1") (pin "32") (pinfunction "NHET08_32") (pintype "passive"))
    )
    (net (code "100") (name "unconnected-(H1-NHET10-Pad40)") (class "Default")
      (node (ref "H1") (pin "40") (pinfunction "NHET10_40") (pintype "passive"))
    )
    (net (code "101") (name "unconnected-(H1-NHET12-Pad42)") (class "Default")
      (node (ref "H1") (pin "42") (pinfunction "NHET12_42") (pintype "passive"))
    )
    (net (code "102") (name "unconnected-(H1-NHET14-Pad44)") (class "Default")
      (node (ref "H1") (pin "44") (pinfunction "NHET14_44") (pintype "passive"))
    )
    (net (code "103") (name "unconnected-(H1-NHET16-Pad46)") (class "Default")
      (node (ref "H1") (pin "46") (pinfunction "NHET16_46") (pintype "passive"))
    )
    (net (code "104") (name "unconnected-(H1-NHET18-Pad48)") (class "Default")
      (node (ref "H1") (pin "48") (pinfunction "NHET18_48") (pintype "passive"))
    )
    (net (code "105") (name "unconnected-(H1-NHET22-Pad50)") (class "Default")
      (node (ref "H1") (pin "50") (pinfunction "NHET22_50") (pintype "passive"))
    )
    (net (code "106") (name "unconnected-(H1-NHET24-Pad33)") (class "Default")
      (node (ref "H1") (pin "33") (pinfunction "NHET24_33") (pintype "passive"))
    )
    (net (code "107") (name "unconnected-(H1-RESET-Pad39)") (class "Default")
      (node (ref "H1") (pin "39") (pinfunction "RESET_39") (pintype "passive"))
    )
    (net (code "108") (name "unconnected-(H1-SCI1_RX-Pad66)") (class "Default")
      (node (ref "H1") (pin "66") (pinfunction "SCI1_RX_66") (pintype "passive"))
    )
    (net (code "109") (name "unconnected-(H1-SCI1_TX-Pad64)") (class "Default")
      (node (ref "H1") (pin "64") (pinfunction "SCI1_TX_64") (pintype "passive"))
    )
    (net (code "110") (name "unconnected-(H1-SPI1CLK-Pad58)") (class "Default")
      (node (ref "H1") (pin "58") (pinfunction "SPI1CLK_58") (pintype "passive"))
    )
    (net (code "111") (name "unconnected-(H1-SPI1CS0-Pad15)") (class "Default")
      (node (ref "H1") (pin "15") (pinfunction "SPI1CS0_15") (pintype "passive"))
    )
    (net (code "112") (name "unconnected-(H1-SPI1CS1-Pad18)") (class "Default")
      (node (ref "H1") (pin "18") (pinfunction "SPI1CS1_18") (pintype "passive"))
    )
    (net (code "113") (name "unconnected-(H1-SPI1CS1-Pad56)") (class "Default")
      (node (ref "H1") (pin "56") (pinfunction "SPI1CS1_56") (pintype "passive"))
    )
    (net (code "114") (name "unconnected-(H1-SPI1CS2-Pad54)") (class "Default")
      (node (ref "H1") (pin "54") (pinfunction "SPI1CS2_54") (pintype "passive"))
    )
    (net (code "115") (name "unconnected-(H1-SPI1CS3-Pad52)") (class "Default")
      (node (ref "H1") (pin "52") (pinfunction "SPI1CS3_52") (pintype "passive"))
    )
    (net (code "116") (name "unconnected-(H1-SPI1ENA-Pad76)") (class "Default")
      (node (ref "H1") (pin "76") (pinfunction "SPI1ENA_76") (pintype "passive"))
    )
    (net (code "117") (name "unconnected-(H1-SPI1SIMO-Pad78)") (class "Default")
      (node (ref "H1") (pin "78") (pinfunction "SPI1SIMO_78") (pintype "passive"))
    )
    (net (code "118") (name "unconnected-(H1-SPI1SOMI-Pad75)") (class "Default")
      (node (ref "H1") (pin "75") (pinfunction "SPI1SOMI_75") (pintype "passive"))
    )
    (net (code "119") (name "unconnected-(H1-SPI2CLK-Pad23)") (class "Default")
      (node (ref "H1") (pin "23") (pinfunction "SPI2CLK_23") (pintype "passive"))
    )
    (net (code "120") (name "unconnected-(H1-SPI2CS0-Pad22)") (class "Default")
      (node (ref "H1") (pin "22") (pinfunction "SPI2CS0_22") (pintype "passive"))
    )
    (net (code "121") (name "unconnected-(H1-SPI2SIMO-Pad24)") (class "Default")
      (node (ref "H1") (pin "24") (pinfunction "SPI2SIMO_24") (pintype "passive"))
    )
    (net (code "122") (name "unconnected-(H1-SPI2SOMI-Pad21)") (class "Default")
      (node (ref "H1") (pin "21") (pinfunction "SPI2SOMI_21") (pintype "passive"))
    )
    (net (code "123") (name "unconnected-(H1-SPI3ENA-Pad16)") (class "Default")
      (node (ref "H1") (pin "16") (pinfunction "SPI3ENA_16") (pintype "passive"))
    )
    (net (code "124") (name "unconnected-(H1-SPI3SCLK-Pad12)") (class "Default")
      (node (ref "H1") (pin "12") (pinfunction "SPI3SCLK_12") (pintype "passive"))
    )
    (net (code "125") (name "unconnected-(H1-SPI3SIMO-Pad13)") (class "Default")
      (node (ref "H1") (pin "13") (pinfunction "SPI3SIMO_13") (pintype "passive"))
    )
    (net (code "126") (name "unconnected-(H1-SPI3SIMO-Pad14)") (class "Default")
      (node (ref "H1") (pin "14") (pinfunction "SPI3SIMO_14") (pintype "passive"))
    )
    (net (code "127") (name "unconnected-(H1-SPI3SOMI-Pad11)") (class "Default")
      (node (ref "H1") (pin "11") (pinfunction "SPI3SOMI_11") (pintype "passive"))
    )
    (net (code "128") (name "unconnected-(H2-3.3V-Pad70)") (class "Default")
      (node (ref "H2") (pin "70") (pinfunction "3.3V_70") (pintype "passive"))
    )
    (net (code "129") (name "unconnected-(H2-5V-Pad69)") (class "Default")
      (node (ref "H2") (pin "69") (pinfunction "5V_69") (pintype "passive"))
    )
    (net (code "130") (name "unconnected-(H2-5v-Pad2)") (class "Default")
      (node (ref "H2") (pin "2") (pinfunction "5v_2") (pintype "passive"))
    )
    (net (code "131") (name "unconnected-(H2-ADEVT-Pad77)") (class "Default")
      (node (ref "H2") (pin "77") (pinfunction "ADEVT_77") (pintype "passive"))
    )
    (net (code "132") (name "unconnected-(H2-ADIN0-Pad65)") (class "Default")
      (node (ref "H2") (pin "65") (pinfunction "ADIN0_65") (pintype "passive"))
    )
    (net (code "133") (name "unconnected-(H2-ADIN1-Pad63)") (class "Default")
      (node (ref "H2") (pin "63") (pinfunction "ADIN1_63") (pintype "passive"))
    )
    (net (code "134") (name "unconnected-(H2-ADIN2-Pad61)") (class "Default")
      (node (ref "H2") (pin "61") (pinfunction "ADIN2_61") (pintype "passive"))
    )
    (net (code "135") (name "unconnected-(H2-ADIN3-Pad59)") (class "Default")
      (node (ref "H2") (pin "59") (pinfunction "ADIN3_59") (pintype "passive"))
    )
    (net (code "136") (name "unconnected-(H2-ADIN4-Pad57)") (class "Default")
      (node (ref "H2") (pin "57") (pinfunction "ADIN4_57") (pintype "passive"))
    )
    (net (code "137") (name "unconnected-(H2-ADIN5-Pad55)") (class "Default")
      (node (ref "H2") (pin "55") (pinfunction "ADIN5_55") (pintype "passive"))
    )
    (net (code "138") (name "unconnected-(H2-ADIN6-Pad6)") (class "Default")
      (node (ref "H2") (pin "6") (pinfunction "ADIN6_6") (pintype "passive"))
    )
    (net (code "139") (name "unconnected-(H2-ADIN6-Pad53)") (class "Default")
      (node (ref "H2") (pin "53") (pinfunction "ADIN6_53") (pintype "passive"))
    )
    (net (code "140") (name "unconnected-(H2-ADIN7-Pad5)") (class "Default")
      (node (ref "H2") (pin "5") (pinfunction "ADIN7_5") (pintype "passive"))
    )
    (net (code "141") (name "unconnected-(H2-ADIN7-Pad51)") (class "Default")
      (node (ref "H2") (pin "51") (pinfunction "ADIN7_51") (pintype "passive"))
    )
    (net (code "142") (name "unconnected-(H2-ADIN8-Pad68)") (class "Default")
      (node (ref "H2") (pin "68") (pinfunction "ADIN8_68") (pintype "passive"))
    )
    (net (code "143") (name "unconnected-(H2-ADIN10-Pad72)") (class "Default")
      (node (ref "H2") (pin "72") (pinfunction "ADIN10_72") (pintype "passive"))
    )
    (net (code "144") (name "unconnected-(H2-ADIN11-Pad73)") (class "Default")
      (node (ref "H2") (pin "73") (pinfunction "ADIN11_73") (pintype "passive"))
    )
    (net (code "145") (name "unconnected-(H2-ADIN21-Pad7)") (class "Default")
      (node (ref "H2") (pin "7") (pinfunction "ADIN21_7") (pintype "passive"))
    )
    (net (code "146") (name "unconnected-(H2-ADIN22-Pad8)") (class "Default")
      (node (ref "H2") (pin "8") (pinfunction "ADIN22_8") (pintype "passive"))
    )
    (net (code "147") (name "unconnected-(H2-CAN2RX-Pad27)") (class "Default")
      (node (ref "H2") (pin "27") (pinfunction "CAN2RX_27") (pintype "passive"))
    )
    (net (code "148") (name "unconnected-(H2-CAN2TX-Pad28)") (class "Default")
      (node (ref "H2") (pin "28") (pinfunction "CAN2TX_28") (pintype "passive"))
    )
    (net (code "149") (name "unconnected-(H2-ECLK-Pad74)") (class "Default")
      (node (ref "H2") (pin "74") (pinfunction "ECLK_74") (pintype "passive"))
    )
    (net (code "150") (name "unconnected-(H2-GND-Pad3)") (class "Default")
      (node (ref "H2") (pin "3") (pinfunction "GND_3") (pintype "passive"))
    )
    (net (code "151") (name "unconnected-(H2-GND-Pad4)") (class "Default")
      (node (ref "H2") (pin "4") (pinfunction "GND_4") (pintype "passive"))
    )
    (net (code "152") (name "unconnected-(H2-GND-Pad9)") (class "Default")
      (node (ref "H2") (pin "9") (pinfunction "GND_9") (pintype "passive"))
    )
    (net (code "153") (name "unconnected-(H2-GND-Pad10)") (class "Default")
      (node (ref "H2") (pin "10") (pinfunction "GND_10") (pintype "passive"))
    )
    (net (code "154") (name "unconnected-(H2-GND-Pad19)") (class "Default")
      (node (ref "H2") (pin "19") (pinfunction "GND_19") (pintype "passive"))
    )
    (net (code "155") (name "unconnected-(H2-GND-Pad20)") (class "Default")
      (node (ref "H2") (pin "20") (pinfunction "GND_20") (pintype "passive"))
    )
    (net (code "156") (name "unconnected-(H2-GND-Pad29)") (class "Default")
      (node (ref "H2") (pin "29") (pinfunction "GND_29") (pintype "passive"))
    )
    (net (code "157") (name "unconnected-(H2-GND-Pad30)") (class "Default")
      (node (ref "H2") (pin "30") (pinfunction "GND_30") (pintype "passive"))
    )
    (net (code "158") (name "unconnected-(H2-GND-Pad31)") (class "Default")
      (node (ref "H2") (pin "31") (pinfunction "GND_31") (pintype "passive"))
    )
    (net (code "159") (name "unconnected-(H2-GND-Pad67)") (class "Default")
      (node (ref "H2") (pin "67") (pinfunction "GND_67") (pintype "passive"))
    )
    (net (code "160") (name "unconnected-(H2-J6-2-Pad62)") (class "Default")
      (node (ref "H2") (pin "62") (pinfunction "J6-2_62") (pintype "passive"))
    )
    (net (code "161") (name "unconnected-(H2-J7-2-Pad60)") (class "Default")
      (node (ref "H2") (pin "60") (pinfunction "J7-2_60") (pintype "passive"))
    )
    (net (code "162") (name "unconnected-(H2-J8-2-Pad43)") (class "Default")
      (node (ref "H2") (pin "43") (pinfunction "J8-2_43") (pintype "passive"))
    )
    (net (code "163") (name "unconnected-(H2-J9-2-Pad41)") (class "Default")
      (node (ref "H2") (pin "41") (pinfunction "J9-2_41") (pintype "passive"))
    )
    (net (code "164") (name "unconnected-(H2-NHET02-Pad34)") (class "Default")
      (node (ref "H2") (pin "34") (pinfunction "NHET02_34") (pintype "passive"))
    )
    (net (code "165") (name "unconnected-(H2-NHET04-Pad36)") (class "Default")
      (node (ref "H2") (pin "36") (pinfunction "NHET04_36") (pintype "passive"))
    )
    (net (code "166") (name "unconnected-(H2-NHET06-Pad38)") (class "Default")
      (node (ref "H2") (pin "38") (pinfunction "NHET06_38") (pintype "passive"))
    )
    (net (code "167") (name "unconnected-(H2-NHET08-Pad32)") (class "Default")
      (node (ref "H2") (pin "32") (pinfunction "NHET08_32") (pintype "passive"))
    )
    (net (code "168") (name "unconnected-(H2-NHET10-Pad40)") (class "Default")
      (node (ref "H2") (pin "40") (pinfunction "NHET10_40") (pintype "passive"))
    )
    (net (code "169") (name "unconnected-(H2-NHET12-Pad42)") (class "Default")
      (node (ref "H2") (pin "42") (pinfunction "NHET12_42") (pintype "passive"))
    )
    (net (code "170") (name "unconnected-(H2-NHET14-Pad44)") (class "Default")
      (node (ref "H2") (pin "44") (pinfunction "NHET14_44") (pintype "passive"))
    )
    (net (code "171") (name "unconnected-(H2-NHET16-Pad46)") (class "Default")
      (node (ref "H2") (pin "46") (pinfunction "NHET16_46") (pintype "passive"))
    )
    (net (code "172") (name "unconnected-(H2-NHET18-Pad48)") (class "Default")
      (node (ref "H2") (pin "48") (pinfunction "NHET18_48") (pintype "passive"))
    )
    (net (code "173") (name "unconnected-(H2-NHET22-Pad50)") (class "Default")
      (node (ref "H2") (pin "50") (pinfunction "NHET22_50") (pintype "passive"))
    )
    (net (code "174") (name "unconnected-(H2-NHET24-Pad33)") (class "Default")
      (node (ref "H2") (pin "33") (pinfunction "NHET24_33") (pintype "passive"))
    )
    (net (code "175") (name "unconnected-(H2-RESET-Pad39)") (class "Default")
      (node (ref "H2") (pin "39") (pinfunction "RESET_39") (pintype "passive"))
    )
    (net (code "176") (name "unconnected-(H2-SCI1_RX-Pad66)") (class "Default")
      (node (ref "H2") (pin "66") (pinfunction "SCI1_RX_66") (pintype "passive"))
    )
    (net (code "177") (name "unconnected-(H2-SCI1_TX-Pad64)") (class "Default")
      (node (ref "H2") (pin "64") (pinfunction "SCI1_TX_64") (pintype "passive"))
    )
    (net (code "178") (name "unconnected-(H2-SPI1CLK-Pad58)") (class "Default")
      (node (ref "H2") (pin "58") (pinfunction "SPI1CLK_58") (pintype "passive"))
    )
    (net (code "179") (name "unconnected-(H2-SPI1CS0-Pad15)") (class "Default")
      (node (ref "H2") (pin "15") (pinfunction "SPI1CS0_15") (pintype "passive"))
    )
    (net (code "180") (name "unconnected-(H2-SPI1CS1-Pad18)") (class "Default")
      (node (ref "H2") (pin "18") (pinfunction "SPI1CS1_18") (pintype "passive"))
    )
    (net (code "181") (name "unconnected-(H2-SPI1CS1-Pad56)") (class "Default")
      (node (ref "H2") (pin "56") (pinfunction "SPI1CS1_56") (pintype "passive"))
    )
    (net (code "182") (name "unconnected-(H2-SPI1CS2-Pad54)") (class "Default")
      (node (ref "H2") (pin "54") (pinfunction "SPI1CS2_54") (pintype "passive"))
    )
    (net (code "183") (name "unconnected-(H2-SPI1CS3-Pad52)") (class "Default")
      (node (ref "H2") (pin "52") (pinfunction "SPI1CS3_52") (pintype "passive"))
    )
    (net (code "184") (name "unconnected-(H2-SPI1ENA-Pad76)") (class "Default")
      (node (ref "H2") (pin "76") (pinfunction "SPI1ENA_76") (pintype "passive"))
    )
    (net (code "185") (name "unconnected-(H2-SPI1SIMO-Pad78)") (class "Default")
      (node (ref "H2") (pin "78") (pinfunction "SPI1SIMO_78") (pintype "passive"))
    )
    (net (code "186") (name "unconnected-(H2-SPI1SOMI-Pad75)") (class "Default")
      (node (ref "H2") (pin "75") (pinfunction "SPI1SOMI_75") (pintype "passive"))
    )
    (net (code "187") (name "unconnected-(H2-SPI2CLK-Pad23)") (class "Default")
      (node (ref "H2") (pin "23") (pinfunction "SPI2CLK_23") (pintype "passive"))
    )
    (net (code "188") (name "unconnected-(H2-SPI2CS0-Pad22)") (class "Default")
      (node (ref "H2") (pin "22") (pinfunction "SPI2CS0_22") (pintype "passive"))
    )
    (net (code "189") (name "unconnected-(H2-SPI2SIMO-Pad24)") (class "Default")
      (node (ref "H2") (pin "24") (pinfunction "SPI2SIMO_24") (pintype "passive"))
    )
    (net (code "190") (name "unconnected-(H2-SPI2SOMI-Pad21)") (class "Default")
      (node (ref "H2") (pin "21") (pinfunction "SPI2SOMI_21") (pintype "passive"))
    )
    (net (code "191") (name "unconnected-(H2-SPI3ENA-Pad16)") (class "Default")
      (node (ref "H2") (pin "16") (pinfunction "SPI3ENA_16") (pintype "passive"))
    )
    (net (code "192") (name "unconnected-(H2-SPI3SCLK-Pad12)") (class "Default")
      (node (ref "H2") (pin "12") (pinfunction "SPI3SCLK_12") (pintype "passive"))
    )
    (net (code "193") (name "unconnected-(H2-SPI3SIMO-Pad13)") (class "Default")
      (node (ref "H2") (pin "13") (pinfunction "SPI3SIMO_13") (pintype "passive"))
    )
    (net (code "194") (name "unconnected-(H2-SPI3SIMO-Pad14)") (class "Default")
      (node (ref "H2") (pin "14") (pinfunction "SPI3SIMO_14") (pintype "passive"))
    )
    (net (code "195") (name "unconnected-(H2-SPI3SOMI-Pad11)") (class "Default")
      (node (ref "H2") (pin "11") (pinfunction "SPI3SOMI_11") (pintype "passive"))
    )
    (net (code "196") (name "unconnected-(IDC34-Pad28)") (class "Default")
      (node (ref "IDC34") (pin "28") (pinfunction "28_28") (pintype "passive"))
    )
    (net (code "197") (name "unconnected-(IDC34-Pad29)") (class "Default")
      (node (ref "IDC34") (pin "29") (pinfunction "29_29") (pintype "passive"))
    )
    (net (code "198") (name "unconnected-(IDC34-Pad30)") (class "Default")
      (node (ref "IDC34") (pin "30") (pinfunction "30_30") (pintype "passive"))
    )
    (net (code "199") (name "unconnected-(IDC34-Pad31)") (class "Default")
      (node (ref "IDC34") (pin "31") (pinfunction "31_31") (pintype "passive"))
    )
    (net (code "200") (name "unconnected-(IDC34-Pad32)") (class "Default")
      (node (ref "IDC34") (pin "32") (pinfunction "32_32") (pintype "passive"))
    )
    (net (code "201") (name "unconnected-(IDC34-Pad33)") (class "Default")
      (node (ref "IDC34") (pin "33") (pinfunction "33_33") (pintype "passive"))
    )
    (net (code "202") (name "unconnected-(IDC34-Pad34)") (class "Default")
      (node (ref "IDC34") (pin "34") (pinfunction "34_34") (pintype "passive"))
    )
    (net (code "203") (name "unconnected-(R3-Pad2)") (class "Default")
      (node (ref "R3") (pin "2") (pinfunction "2_2") (pintype "passive"))
    )
    (net (code "204") (name "unconnected-(R4-Pad2)") (class "Default")
      (node (ref "R4") (pin "2") (pinfunction "2_2") (pintype "passive"))
    )
    (net (code "205") (name "unconnected-(R6-Pad4)") (class "Default")
      (node (ref "R6") (pin "4") (pinfunction "4_4") (pintype "passive"))
    )
    (net (code "206") (name "unconnected-(R7-Pad2)") (class "Default")
      (node (ref "R7") (pin "2") (pinfunction "2_2") (pintype "passive"))
    )
    (net (code "207") (name "unconnected-(R8-Pad2)") (class "Default")
      (node (ref "R8") (pin "2") (pinfunction "2_2") (pintype "passive"))
    )
    (net (code "208") (name "unconnected-(R9-Pad2)") (class "Default")
      (node (ref "R9") (pin "2") (pinfunction "2_2") (pintype "passive"))
    )
    (net (code "209") (name "unconnected-(R10-Pad2)") (class "Default")
      (node (ref "R10") (pin "2") (pinfunction "2_2") (pintype "passive"))
    )
    (net (code "210") (name "unconnected-(R11-Pad2)") (class "Default")
      (node (ref "R11") (pin "2") (pinfunction "2_2") (pintype "passive"))
    )
    (net (code "211") (name "unconnected-(R12-Pad2)") (class "Default")
      (node (ref "R12") (pin "2") (pinfunction "2_2") (pintype "passive"))
    )
    (net (code "212") (name "unconnected-(R13-Pad2)") (class "Default")
      (node (ref "R13") (pin "2") (pinfunction "2_2") (pintype "passive"))
    )
    (net (code "213") (name "unconnected-(R14-Pad2)") (class "Default")
      (node (ref "R14") (pin "2") (pinfunction "2_2") (pintype "passive"))
    )
    (net (code "214") (name "unconnected-(R15-Pad2)") (class "Default")
      (node (ref "R15") (pin "2") (pinfunction "2_2") (pintype "passive"))
    )
    (net (code "215") (name "unconnected-(R16-Pad2)") (class "Default")
      (node (ref "R16") (pin "2") (pinfunction "2_2") (pintype "passive"))
    )
    (net (code "216") (name "unconnected-(R17-Pad2)") (class "Default")
      (node (ref "R17") (pin "2") (pinfunction "2_2") (pintype "passive"))
    )
    (net (code "217") (name "unconnected-(R18-Pad2)") (class "Default")
      (node (ref "R18") (pin "2") (pinfunction "2_2") (pintype "passive"))
    )
    (net (code "218") (name "unconnected-(R19-Pad2)") (class "Default")
      (node (ref "R19") (pin "2") (pinfunction "2_2") (pintype "passive"))
    )
    (net (code "219") (name "unconnected-(TB1-+5V-Pad31)") (class "Default")
      (node (ref "TB1") (pin "31") (pinfunction "+5V_31") (pintype "passive"))
    )
    (net (code "220") (name "unconnected-(TB1-3v3-Pad30)") (class "Default")
      (node (ref "TB1") (pin "30") (pinfunction "3v3_30") (pintype "passive"))
    )
    (net (code "221") (name "unconnected-(TB1-A1-Pad14)") (class "Default")
      (node (ref "TB1") (pin "14") (pinfunction "A1_14") (pintype "passive"))
    )
    (net (code "222") (name "unconnected-(TB1-A2-Pad13)") (class "Default")
      (node (ref "TB1") (pin "13") (pinfunction "A2_13") (pintype "passive"))
    )
    (net (code "223") (name "unconnected-(TB1-A3-Pad12)") (class "Default")
      (node (ref "TB1") (pin "12") (pinfunction "A3_12") (pintype "passive"))
    )
    (net (code "224") (name "unconnected-(TB1-A4-Pad11)") (class "Default")
      (node (ref "TB1") (pin "11") (pinfunction "A4_11") (pintype "passive"))
    )
    (net (code "225") (name "unconnected-(TB1-A5-Pad10)") (class "Default")
      (node (ref "TB1") (pin "10") (pinfunction "A5_10") (pintype "passive"))
    )
    (net (code "226") (name "unconnected-(TB1-A6-Pad9)") (class "Default")
      (node (ref "TB1") (pin "9") (pinfunction "A6_9") (pintype "passive"))
    )
    (net (code "227") (name "unconnected-(TB1-A7-Pad8)") (class "Default")
      (node (ref "TB1") (pin "8") (pinfunction "A7_8") (pintype "passive"))
    )
    (net (code "228") (name "unconnected-(TB1-AREF-Pad29)") (class "Default")
      (node (ref "TB1") (pin "29") (pinfunction "AREF_29") (pintype "passive"))
    )
    (net (code "229") (name "unconnected-(TB1-COM{slash}GND-Pad20)") (class "Default")
      (node (ref "TB1") (pin "20") (pinfunction "COM/GND_20") (pintype "passive"))
    )
    (net (code "230") (name "unconnected-(TB1-D0{slash}RX-Pad7)") (class "Default")
      (node (ref "TB1") (pin "7") (pinfunction "D0/RX_7") (pintype "passive"))
    )
    (net (code "231") (name "unconnected-(TB1-D1{slash}TX-Pad6)") (class "Default")
      (node (ref "TB1") (pin "6") (pinfunction "D1/TX_6") (pintype "passive"))
    )
    (net (code "232") (name "unconnected-(TB1-D3-Pad4)") (class "Default")
      (node (ref "TB1") (pin "4") (pinfunction "D3_4") (pintype "passive"))
    )
    (net (code "233") (name "unconnected-(TB1-D4-Pad3)") (class "Default")
      (node (ref "TB1") (pin "3") (pinfunction "D4_3") (pintype "passive"))
    )
    (net (code "234") (name "unconnected-(TB1-D5-Pad2)") (class "Default")
      (node (ref "TB1") (pin "2") (pinfunction "D5_2") (pintype "passive"))
    )
    (net (code "235") (name "unconnected-(TB1-D6-Pad1)") (class "Default")
      (node (ref "TB1") (pin "1") (pinfunction "D6_1") (pintype "passive"))
    )
    (net (code "236") (name "unconnected-(TB1-D7-Pad28)") (class "Default")
      (node (ref "TB1") (pin "28") (pinfunction "D7_28") (pintype "passive"))
    )
    (net (code "237") (name "unconnected-(TB1-D8-Pad26)") (class "Default")
      (node (ref "TB1") (pin "26") (pinfunction "D8_26") (pintype "passive"))
    )
    (net (code "238") (name "unconnected-(TB1-D9-Pad25)") (class "Default")
      (node (ref "TB1") (pin "25") (pinfunction "D9_25") (pintype "passive"))
    )
    (net (code "239") (name "unconnected-(TB1-D10-Pad24)") (class "Default")
      (node (ref "TB1") (pin "24") (pinfunction "D10_24") (pintype "passive"))
    )
    (net (code "240") (name "unconnected-(TB1-D11{slash}MISO-Pad23)") (class "Default")
      (node (ref "TB1") (pin "23") (pinfunction "D11/MISO_23") (pintype "passive"))
    )
    (net (code "241") (name "unconnected-(TB1-D12{slash}MISO-Pad22)") (class "Default")
      (node (ref "TB1") (pin "22") (pinfunction "D12/MISO_22") (pintype "passive"))
    )
    (net (code "242") (name "unconnected-(TB1-D13{slash}SCK-Pad21)") (class "Default")
      (node (ref "TB1") (pin "21") (pinfunction "D13/SCK_21") (pintype "passive"))
    )
    (net (code "243") (name "unconnected-(TB1-RESET-Pad16)") (class "Default")
      (node (ref "TB1") (pin "16") (pinfunction "RESET_16") (pintype "passive"))
    )
    (net (code "244") (name "unconnected-(TB1-RESET-Pad17)") (class "Default")
      (node (ref "TB1") (pin "17") (pinfunction "RESET_17") (pintype "passive"))
    )
    (net (code "245") (name "unconnected-(ULN1-GND-Pad9)") (class "Default")
      (node (ref "ULN1") (pin "9") (pinfunction "GND_9") (pintype "passive"))
    )
    (net (code "246") (name "unconnected-(ULN2-GND-Pad9)") (class "Default")
      (node (ref "ULN2") (pin "9") (pinfunction "GND_9") (pintype "passive"))
    )
    (net (code "247") (name "unconnected-(ULN3-GND-Pad9)") (class "Default")
      (node (ref "ULN3") (pin "9") (pinfunction "GND_9") (pintype "passive"))
    )
  )
)
